# d150_z570m_rev_a.net
KiCad netlist of a schematic drawn in EAGLE
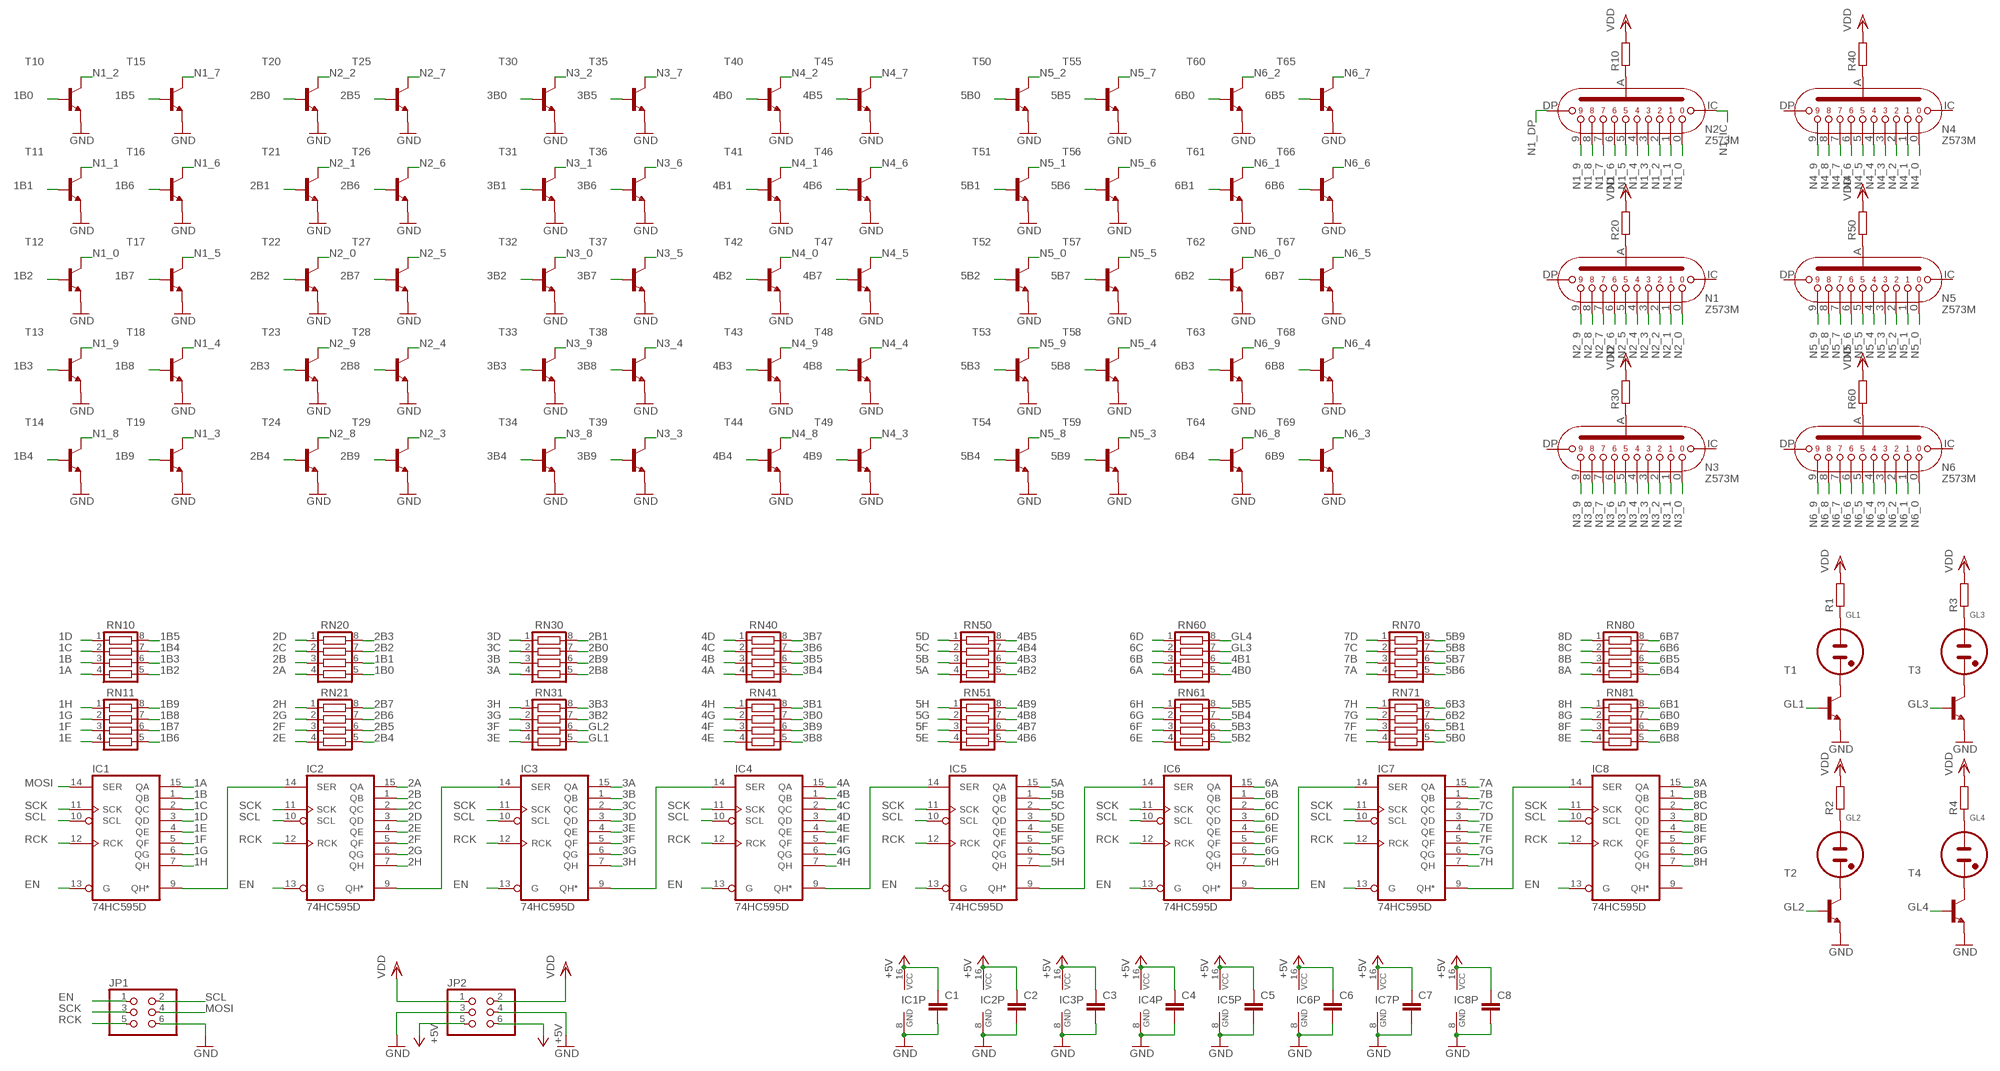
[diagram p0: schematic, sheet 1]

(export (version "E")
  (design (tool "Eeschema 10.0.6"))
  (components
    (comp (ref "C1")
      (value "C-EUC0603")
      (footprint "eagle-import:C0603")
      (libsource (lib "eagle-import") (part "C-EUC0603"))
    )
    (comp (ref "C2")
      (value "C-EUC0603")
      (footprint "eagle-import:C0603")
      (libsource (lib "eagle-import") (part "C-EUC0603"))
    )
    (comp (ref "C3")
      (value "C-EUC0603")
      (footprint "eagle-import:C0603")
      (libsource (lib "eagle-import") (part "C-EUC0603"))
    )
    (comp (ref "C4")
      (value "C-EUC0603")
      (footprint "eagle-import:C0603")
      (libsource (lib "eagle-import") (part "C-EUC0603"))
    )
    (comp (ref "C5")
      (value "C-EUC0603")
      (footprint "eagle-import:C0603")
      (libsource (lib "eagle-import") (part "C-EUC0603"))
    )
    (comp (ref "C6")
      (value "C-EUC0603")
      (footprint "eagle-import:C0603")
      (libsource (lib "eagle-import") (part "C-EUC0603"))
    )
    (comp (ref "C7")
      (value "C-EUC0603")
      (footprint "eagle-import:C0603")
      (libsource (lib "eagle-import") (part "C-EUC0603"))
    )
    (comp (ref "C8")
      (value "C-EUC0603")
      (footprint "eagle-import:C0603")
      (libsource (lib "eagle-import") (part "C-EUC0603"))
    )
    (comp (ref "GL1")
      (value "NE2-NEON-BULB-DRILL")
      (footprint "eagle-import:NE2-NEON-BULB-DRILL")
      (libsource (lib "eagle-import") (part "NE2-NEON-BULB-DRILL"))
    )
    (comp (ref "GL2")
      (value "NE2-NEON-BULB-DRILL")
      (footprint "eagle-import:NE2-NEON-BULB-DRILL")
      (libsource (lib "eagle-import") (part "NE2-NEON-BULB-DRILL"))
    )
    (comp (ref "GL3")
      (value "NE2-NEON-BULB-DRILL")
      (footprint "eagle-import:NE2-NEON-BULB-DRILL")
      (libsource (lib "eagle-import") (part "NE2-NEON-BULB-DRILL"))
    )
    (comp (ref "GL4")
      (value "NE2-NEON-BULB-DRILL")
      (footprint "eagle-import:NE2-NEON-BULB-DRILL")
      (libsource (lib "eagle-import") (part "NE2-NEON-BULB-DRILL"))
    )
    (comp (ref "IC1")
      (value "74HC595D")
      (footprint "eagle-import:SO16")
      (libsource (lib "eagle-import") (part "74595DHC"))
    )
    (comp (ref "IC2")
      (value "74HC595D")
      (footprint "eagle-import:SO16")
      (libsource (lib "eagle-import") (part "74595DHC"))
    )
    (comp (ref "IC3")
      (value "74HC595D")
      (footprint "eagle-import:SO16")
      (libsource (lib "eagle-import") (part "74595DHC"))
    )
    (comp (ref "IC4")
      (value "74HC595D")
      (footprint "eagle-import:SO16")
      (libsource (lib "eagle-import") (part "74595DHC"))
    )
    (comp (ref "IC5")
      (value "74HC595D")
      (footprint "eagle-import:SO16")
      (libsource (lib "eagle-import") (part "74595DHC"))
    )
    (comp (ref "IC6")
      (value "74HC595D")
      (footprint "eagle-import:SO16")
      (libsource (lib "eagle-import") (part "74595DHC"))
    )
    (comp (ref "IC7")
      (value "74HC595D")
      (footprint "eagle-import:SO16")
      (libsource (lib "eagle-import") (part "74595DHC"))
    )
    (comp (ref "IC8")
      (value "74HC595D")
      (footprint "eagle-import:SO16")
      (libsource (lib "eagle-import") (part "74595DHC"))
    )
    (comp (ref "JP1")
      (value "PINHD-2X3_2.54-SMD")
      (footprint "eagle-import:2X03SMD")
      (libsource (lib "eagle-import") (part "PINHD-2X3_2.54-SMD"))
    )
    (comp (ref "JP2")
      (value "PINHD-2X3_2.54-SMD")
      (footprint "eagle-import:2X03SMD")
      (libsource (lib "eagle-import") (part "PINHD-2X3_2.54-SMD"))
    )
    (comp (ref "N1")
      (value "Z573M")
      (footprint "eagle-import:Z57XX")
      (libsource (lib "eagle-import") (part "Z573M"))
    )
    (comp (ref "N2")
      (value "Z573M")
      (footprint "eagle-import:Z57XX")
      (libsource (lib "eagle-import") (part "Z573M"))
    )
    (comp (ref "N3")
      (value "Z573M")
      (footprint "eagle-import:Z57XX")
      (libsource (lib "eagle-import") (part "Z573M"))
    )
    (comp (ref "N4")
      (value "Z573M")
      (footprint "eagle-import:Z57XX")
      (libsource (lib "eagle-import") (part "Z573M"))
    )
    (comp (ref "N5")
      (value "Z573M")
      (footprint "eagle-import:Z57XX")
      (libsource (lib "eagle-import") (part "Z573M"))
    )
    (comp (ref "N6")
      (value "Z573M")
      (footprint "eagle-import:Z57XX")
      (libsource (lib "eagle-import") (part "Z573M"))
    )
    (comp (ref "R1")
      (value "R-EU_R0603")
      (footprint "eagle-import:R0603")
      (libsource (lib "eagle-import") (part "R-EU_R0603"))
    )
    (comp (ref "R2")
      (value "R-EU_R0603")
      (footprint "eagle-import:R0603")
      (libsource (lib "eagle-import") (part "R-EU_R0603"))
    )
    (comp (ref "R3")
      (value "R-EU_R0603")
      (footprint "eagle-import:R0603")
      (libsource (lib "eagle-import") (part "R-EU_R0603"))
    )
    (comp (ref "R4")
      (value "R-EU_R0603")
      (footprint "eagle-import:R0603")
      (libsource (lib "eagle-import") (part "R-EU_R0603"))
    )
    (comp (ref "R10")
      (value "R-EU_R0603")
      (footprint "eagle-import:R0603")
      (libsource (lib "eagle-import") (part "R-EU_R0603"))
    )
    (comp (ref "R20")
      (value "R-EU_R0603")
      (footprint "eagle-import:R0603")
      (libsource (lib "eagle-import") (part "R-EU_R0603"))
    )
    (comp (ref "R30")
      (value "R-EU_R0603")
      (footprint "eagle-import:R0603")
      (libsource (lib "eagle-import") (part "R-EU_R0603"))
    )
    (comp (ref "R40")
      (value "R-EU_R0603")
      (footprint "eagle-import:R0603")
      (libsource (lib "eagle-import") (part "R-EU_R0603"))
    )
    (comp (ref "R50")
      (value "R-EU_R0603")
      (footprint "eagle-import:R0603")
      (libsource (lib "eagle-import") (part "R-EU_R0603"))
    )
    (comp (ref "R60")
      (value "R-EU_R0603")
      (footprint "eagle-import:R0603")
      (libsource (lib "eagle-import") (part "R-EU_R0603"))
    )
    (comp (ref "RN10")
      (value "CTS742C083")
      (footprint "eagle-import:CTS742C083")
      (fields (field (name "OC_FARNELL") "unknown") (field (name "OC_NEWARK") "unknown"))
      (libsource (lib "eagle-import") (part "CTS742C083"))
    )
    (comp (ref "RN11")
      (value "CTS742C083")
      (footprint "eagle-import:CTS742C083")
      (fields (field (name "OC_FARNELL") "unknown") (field (name "OC_NEWARK") "unknown"))
      (libsource (lib "eagle-import") (part "CTS742C083"))
    )
    (comp (ref "RN20")
      (value "CTS742C083")
      (footprint "eagle-import:CTS742C083")
      (fields (field (name "OC_FARNELL") "unknown") (field (name "OC_NEWARK") "unknown"))
      (libsource (lib "eagle-import") (part "CTS742C083"))
    )
    (comp (ref "RN21")
      (value "CTS742C083")
      (footprint "eagle-import:CTS742C083")
      (fields (field (name "OC_FARNELL") "unknown") (field (name "OC_NEWARK") "unknown"))
      (libsource (lib "eagle-import") (part "CTS742C083"))
    )
    (comp (ref "RN30")
      (value "CTS742C083")
      (footprint "eagle-import:CTS742C083")
      (fields (field (name "OC_FARNELL") "unknown") (field (name "OC_NEWARK") "unknown"))
      (libsource (lib "eagle-import") (part "CTS742C083"))
    )
    (comp (ref "RN31")
      (value "CTS742C083")
      (footprint "eagle-import:CTS742C083")
      (fields (field (name "OC_FARNELL") "unknown") (field (name "OC_NEWARK") "unknown"))
      (libsource (lib "eagle-import") (part "CTS742C083"))
    )
    (comp (ref "RN40")
      (value "CTS742C083")
      (footprint "eagle-import:CTS742C083")
      (fields (field (name "OC_FARNELL") "unknown") (field (name "OC_NEWARK") "unknown"))
      (libsource (lib "eagle-import") (part "CTS742C083"))
    )
    (comp (ref "RN41")
      (value "CTS742C083")
      (footprint "eagle-import:CTS742C083")
      (fields (field (name "OC_FARNELL") "unknown") (field (name "OC_NEWARK") "unknown"))
      (libsource (lib "eagle-import") (part "CTS742C083"))
    )
    (comp (ref "RN50")
      (value "CTS742C083")
      (footprint "eagle-import:CTS742C083")
      (fields (field (name "OC_FARNELL") "unknown") (field (name "OC_NEWARK") "unknown"))
      (libsource (lib "eagle-import") (part "CTS742C083"))
    )
    (comp (ref "RN51")
      (value "CTS742C083")
      (footprint "eagle-import:CTS742C083")
      (fields (field (name "OC_FARNELL") "unknown") (field (name "OC_NEWARK") "unknown"))
      (libsource (lib "eagle-import") (part "CTS742C083"))
    )
    (comp (ref "RN60")
      (value "CTS742C083")
      (footprint "eagle-import:CTS742C083")
      (fields (field (name "OC_FARNELL") "unknown") (field (name "OC_NEWARK") "unknown"))
      (libsource (lib "eagle-import") (part "CTS742C083"))
    )
    (comp (ref "RN61")
      (value "CTS742C083")
      (footprint "eagle-import:CTS742C083")
      (fields (field (name "OC_FARNELL") "unknown") (field (name "OC_NEWARK") "unknown"))
      (libsource (lib "eagle-import") (part "CTS742C083"))
    )
    (comp (ref "RN70")
      (value "CTS742C083")
      (footprint "eagle-import:CTS742C083")
      (fields (field (name "OC_FARNELL") "unknown") (field (name "OC_NEWARK") "unknown"))
      (libsource (lib "eagle-import") (part "CTS742C083"))
    )
    (comp (ref "RN71")
      (value "CTS742C083")
      (footprint "eagle-import:CTS742C083")
      (fields (field (name "OC_FARNELL") "unknown") (field (name "OC_NEWARK") "unknown"))
      (libsource (lib "eagle-import") (part "CTS742C083"))
    )
    (comp (ref "RN80")
      (value "CTS742C083")
      (footprint "eagle-import:CTS742C083")
      (fields (field (name "OC_FARNELL") "unknown") (field (name "OC_NEWARK") "unknown"))
      (libsource (lib "eagle-import") (part "CTS742C083"))
    )
    (comp (ref "RN81")
      (value "CTS742C083")
      (footprint "eagle-import:CTS742C083")
      (fields (field (name "OC_FARNELL") "unknown") (field (name "OC_NEWARK") "unknown"))
      (libsource (lib "eagle-import") (part "CTS742C083"))
    )
    (comp (ref "T1")
      (value "SMBTA42")
      (footprint "eagle-import:SOT23")
      (libsource (lib "eagle-import") (part "SMBTA42"))
    )
    (comp (ref "T2")
      (value "SMBTA42")
      (footprint "eagle-import:SOT23")
      (libsource (lib "eagle-import") (part "SMBTA42"))
    )
    (comp (ref "T3")
      (value "SMBTA42")
      (footprint "eagle-import:SOT23")
      (libsource (lib "eagle-import") (part "SMBTA42"))
    )
    (comp (ref "T4")
      (value "SMBTA42")
      (footprint "eagle-import:SOT23")
      (libsource (lib "eagle-import") (part "SMBTA42"))
    )
    (comp (ref "T10")
      (value "SMBTA42")
      (footprint "eagle-import:SOT23")
      (libsource (lib "eagle-import") (part "SMBTA42"))
    )
    (comp (ref "T11")
      (value "SMBTA42")
      (footprint "eagle-import:SOT23")
      (libsource (lib "eagle-import") (part "SMBTA42"))
    )
    (comp (ref "T12")
      (value "SMBTA42")
      (footprint "eagle-import:SOT23")
      (libsource (lib "eagle-import") (part "SMBTA42"))
    )
    (comp (ref "T13")
      (value "SMBTA42")
      (footprint "eagle-import:SOT23")
      (libsource (lib "eagle-import") (part "SMBTA42"))
    )
    (comp (ref "T14")
      (value "SMBTA42")
      (footprint "eagle-import:SOT23")
      (libsource (lib "eagle-import") (part "SMBTA42"))
    )
    (comp (ref "T15")
      (value "SMBTA42")
      (footprint "eagle-import:SOT23")
      (libsource (lib "eagle-import") (part "SMBTA42"))
    )
    (comp (ref "T16")
      (value "SMBTA42")
      (footprint "eagle-import:SOT23")
      (libsource (lib "eagle-import") (part "SMBTA42"))
    )
    (comp (ref "T17")
      (value "SMBTA42")
      (footprint "eagle-import:SOT23")
      (libsource (lib "eagle-import") (part "SMBTA42"))
    )
    (comp (ref "T18")
      (value "SMBTA42")
      (footprint "eagle-import:SOT23")
      (libsource (lib "eagle-import") (part "SMBTA42"))
    )
    (comp (ref "T19")
      (value "SMBTA42")
      (footprint "eagle-import:SOT23")
      (libsource (lib "eagle-import") (part "SMBTA42"))
    )
    (comp (ref "T20")
      (value "SMBTA42")
      (footprint "eagle-import:SOT23")
      (libsource (lib "eagle-import") (part "SMBTA42"))
    )
    (comp (ref "T21")
      (value "SMBTA42")
      (footprint "eagle-import:SOT23")
      (libsource (lib "eagle-import") (part "SMBTA42"))
    )
    (comp (ref "T22")
      (value "SMBTA42")
      (footprint "eagle-import:SOT23")
      (libsource (lib "eagle-import") (part "SMBTA42"))
    )
    (comp (ref "T23")
      (value "SMBTA42")
      (footprint "eagle-import:SOT23")
      (libsource (lib "eagle-import") (part "SMBTA42"))
    )
    (comp (ref "T24")
      (value "SMBTA42")
      (footprint "eagle-import:SOT23")
      (libsource (lib "eagle-import") (part "SMBTA42"))
    )
    (comp (ref "T25")
      (value "SMBTA42")
      (footprint "eagle-import:SOT23")
      (libsource (lib "eagle-import") (part "SMBTA42"))
    )
    (comp (ref "T26")
      (value "SMBTA42")
      (footprint "eagle-import:SOT23")
      (libsource (lib "eagle-import") (part "SMBTA42"))
    )
    (comp (ref "T27")
      (value "SMBTA42")
      (footprint "eagle-import:SOT23")
      (libsource (lib "eagle-import") (part "SMBTA42"))
    )
    (comp (ref "T28")
      (value "SMBTA42")
      (footprint "eagle-import:SOT23")
      (libsource (lib "eagle-import") (part "SMBTA42"))
    )
    (comp (ref "T29")
      (value "SMBTA42")
      (footprint "eagle-import:SOT23")
      (libsource (lib "eagle-import") (part "SMBTA42"))
    )
    (comp (ref "T30")
      (value "SMBTA42")
      (footprint "eagle-import:SOT23")
      (libsource (lib "eagle-import") (part "SMBTA42"))
    )
    (comp (ref "T31")
      (value "SMBTA42")
      (footprint "eagle-import:SOT23")
      (libsource (lib "eagle-import") (part "SMBTA42"))
    )
    (comp (ref "T32")
      (value "SMBTA42")
      (footprint "eagle-import:SOT23")
      (libsource (lib "eagle-import") (part "SMBTA42"))
    )
    (comp (ref "T33")
      (value "SMBTA42")
      (footprint "eagle-import:SOT23")
      (libsource (lib "eagle-import") (part "SMBTA42"))
    )
    (comp (ref "T34")
      (value "SMBTA42")
      (footprint "eagle-import:SOT23")
      (libsource (lib "eagle-import") (part "SMBTA42"))
    )
    (comp (ref "T35")
      (value "SMBTA42")
      (footprint "eagle-import:SOT23")
      (libsource (lib "eagle-import") (part "SMBTA42"))
    )
    (comp (ref "T36")
      (value "SMBTA42")
      (footprint "eagle-import:SOT23")
      (libsource (lib "eagle-import") (part "SMBTA42"))
    )
    (comp (ref "T37")
      (value "SMBTA42")
      (footprint "eagle-import:SOT23")
      (libsource (lib "eagle-import") (part "SMBTA42"))
    )
    (comp (ref "T38")
      (value "SMBTA42")
      (footprint "eagle-import:SOT23")
      (libsource (lib "eagle-import") (part "SMBTA42"))
    )
    (comp (ref "T39")
      (value "SMBTA42")
      (footprint "eagle-import:SOT23")
      (libsource (lib "eagle-import") (part "SMBTA42"))
    )
    (comp (ref "T40")
      (value "SMBTA42")
      (footprint "eagle-import:SOT23")
      (libsource (lib "eagle-import") (part "SMBTA42"))
    )
    (comp (ref "T41")
      (value "SMBTA42")
      (footprint "eagle-import:SOT23")
      (libsource (lib "eagle-import") (part "SMBTA42"))
    )
    (comp (ref "T42")
      (value "SMBTA42")
      (footprint "eagle-import:SOT23")
      (libsource (lib "eagle-import") (part "SMBTA42"))
    )
    (comp (ref "T43")
      (value "SMBTA42")
      (footprint "eagle-import:SOT23")
      (libsource (lib "eagle-import") (part "SMBTA42"))
    )
    (comp (ref "T44")
      (value "SMBTA42")
      (footprint "eagle-import:SOT23")
      (libsource (lib "eagle-import") (part "SMBTA42"))
    )
    (comp (ref "T45")
      (value "SMBTA42")
      (footprint "eagle-import:SOT23")
      (libsource (lib "eagle-import") (part "SMBTA42"))
    )
    (comp (ref "T46")
      (value "SMBTA42")
      (footprint "eagle-import:SOT23")
      (libsource (lib "eagle-import") (part "SMBTA42"))
    )
    (comp (ref "T47")
      (value "SMBTA42")
      (footprint "eagle-import:SOT23")
      (libsource (lib "eagle-import") (part "SMBTA42"))
    )
    (comp (ref "T48")
      (value "SMBTA42")
      (footprint "eagle-import:SOT23")
      (libsource (lib "eagle-import") (part "SMBTA42"))
    )
    (comp (ref "T49")
      (value "SMBTA42")
      (footprint "eagle-import:SOT23")
      (libsource (lib "eagle-import") (part "SMBTA42"))
    )
    (comp (ref "T50")
      (value "SMBTA42")
      (footprint "eagle-import:SOT23")
      (libsource (lib "eagle-import") (part "SMBTA42"))
    )
    (comp (ref "T51")
      (value "SMBTA42")
      (footprint "eagle-import:SOT23")
      (libsource (lib "eagle-import") (part "SMBTA42"))
    )
    (comp (ref "T52")
      (value "SMBTA42")
      (footprint "eagle-import:SOT23")
      (libsource (lib "eagle-import") (part "SMBTA42"))
    )
    (comp (ref "T53")
      (value "SMBTA42")
      (footprint "eagle-import:SOT23")
      (libsource (lib "eagle-import") (part "SMBTA42"))
    )
    (comp (ref "T54")
      (value "SMBTA42")
      (footprint "eagle-import:SOT23")
      (libsource (lib "eagle-import") (part "SMBTA42"))
    )
    (comp (ref "T55")
      (value "SMBTA42")
      (footprint "eagle-import:SOT23")
      (libsource (lib "eagle-import") (part "SMBTA42"))
    )
    (comp (ref "T56")
      (value "SMBTA42")
      (footprint "eagle-import:SOT23")
      (libsource (lib "eagle-import") (part "SMBTA42"))
    )
    (comp (ref "T57")
      (value "SMBTA42")
      (footprint "eagle-import:SOT23")
      (libsource (lib "eagle-import") (part "SMBTA42"))
    )
    (comp (ref "T58")
      (value "SMBTA42")
      (footprint "eagle-import:SOT23")
      (libsource (lib "eagle-import") (part "SMBTA42"))
    )
    (comp (ref "T59")
      (value "SMBTA42")
      (footprint "eagle-import:SOT23")
      (libsource (lib "eagle-import") (part "SMBTA42"))
    )
    (comp (ref "T60")
      (value "SMBTA42")
      (footprint "eagle-import:SOT23")
      (libsource (lib "eagle-import") (part "SMBTA42"))
    )
    (comp (ref "T61")
      (value "SMBTA42")
      (footprint "eagle-import:SOT23")
      (libsource (lib "eagle-import") (part "SMBTA42"))
    )
    (comp (ref "T62")
      (value "SMBTA42")
      (footprint "eagle-import:SOT23")
      (libsource (lib "eagle-import") (part "SMBTA42"))
    )
    (comp (ref "T63")
      (value "SMBTA42")
      (footprint "eagle-import:SOT23")
      (libsource (lib "eagle-import") (part "SMBTA42"))
    )
    (comp (ref "T64")
      (value "SMBTA42")
      (footprint "eagle-import:SOT23")
      (libsource (lib "eagle-import") (part "SMBTA42"))
    )
    (comp (ref "T65")
      (value "SMBTA42")
      (footprint "eagle-import:SOT23")
      (libsource (lib "eagle-import") (part "SMBTA42"))
    )
    (comp (ref "T66")
      (value "SMBTA42")
      (footprint "eagle-import:SOT23")
      (libsource (lib "eagle-import") (part "SMBTA42"))
    )
    (comp (ref "T67")
      (value "SMBTA42")
      (footprint "eagle-import:SOT23")
      (libsource (lib "eagle-import") (part "SMBTA42"))
    )
    (comp (ref "T68")
      (value "SMBTA42")
      (footprint "eagle-import:SOT23")
      (libsource (lib "eagle-import") (part "SMBTA42"))
    )
    (comp (ref "T69")
      (value "SMBTA42")
      (footprint "eagle-import:SOT23")
      (libsource (lib "eagle-import") (part "SMBTA42"))
    )
  )
  (nets
    (net (code "1") (name "+5V") (class "Default")
      (node (ref "C1") (pin "1") (pinfunction "1_1") (pintype "passive"))
      (node (ref "C2") (pin "1") (pinfunction "1_1") (pintype "passive"))
      (node (ref "C3") (pin "1") (pinfunction "1_1") (pintype "passive"))
      (node (ref "C4") (pin "1") (pinfunction "1_1") (pintype "passive"))
      (node (ref "C5") (pin "1") (pinfunction "1_1") (pintype "passive"))
      (node (ref "C6") (pin "1") (pinfunction "1_1") (pintype "passive"))
      (node (ref "C7") (pin "1") (pinfunction "1_1") (pintype "passive"))
      (node (ref "C8") (pin "1") (pinfunction "1_1") (pintype "passive"))
      (node (ref "IC1") (pin "16") (pinfunction "VCC_16") (pintype "power_in"))
      (node (ref "IC2") (pin "16") (pinfunction "VCC_16") (pintype "power_in"))
      (node (ref "IC3") (pin "16") (pinfunction "VCC_16") (pintype "power_in"))
      (node (ref "IC4") (pin "16") (pinfunction "VCC_16") (pintype "power_in"))
      (node (ref "IC5") (pin "16") (pinfunction "VCC_16") (pintype "power_in"))
      (node (ref "IC6") (pin "16") (pinfunction "VCC_16") (pintype "power_in"))
      (node (ref "IC7") (pin "16") (pinfunction "VCC_16") (pintype "power_in"))
      (node (ref "IC8") (pin "16") (pinfunction "VCC_16") (pintype "power_in"))
      (node (ref "JP2") (pin "5") (pinfunction "5_5") (pintype "passive"))
      (node (ref "JP2") (pin "6") (pinfunction "6_6") (pintype "passive"))
    )
    (net (code "2") (name "/1A") (class "Default")
      (node (ref "IC1") (pin "15") (pinfunction "QA_15") (pintype "tri_state"))
      (node (ref "RN10") (pin "4") (pinfunction "4_4") (pintype "passive"))
    )
    (net (code "3") (name "/1B") (class "Default")
      (node (ref "IC1") (pin "1") (pinfunction "QB_1") (pintype "tri_state"))
      (node (ref "RN10") (pin "3") (pinfunction "3_3") (pintype "passive"))
    )
    (net (code "4") (name "/1B0") (class "Default")
      (node (ref "RN20") (pin "5") (pinfunction "5_5") (pintype "passive"))
      (node (ref "T10") (pin "1") (pinfunction "B_1") (pintype "passive"))
    )
    (net (code "5") (name "/1B1") (class "Default")
      (node (ref "RN20") (pin "6") (pinfunction "6_6") (pintype "passive"))
      (node (ref "T11") (pin "1") (pinfunction "B_1") (pintype "passive"))
    )
    (net (code "6") (name "/1B2") (class "Default")
      (node (ref "RN10") (pin "5") (pinfunction "5_5") (pintype "passive"))
      (node (ref "T12") (pin "1") (pinfunction "B_1") (pintype "passive"))
    )
    (net (code "7") (name "/1B3") (class "Default")
      (node (ref "RN10") (pin "6") (pinfunction "6_6") (pintype "passive"))
      (node (ref "T13") (pin "1") (pinfunction "B_1") (pintype "passive"))
    )
    (net (code "8") (name "/1B4") (class "Default")
      (node (ref "RN10") (pin "7") (pinfunction "7_7") (pintype "passive"))
      (node (ref "T14") (pin "1") (pinfunction "B_1") (pintype "passive"))
    )
    (net (code "9") (name "/1B5") (class "Default")
      (node (ref "RN10") (pin "8") (pinfunction "8_8") (pintype "passive"))
      (node (ref "T15") (pin "1") (pinfunction "B_1") (pintype "passive"))
    )
    (net (code "10") (name "/1B6") (class "Default")
      (node (ref "RN11") (pin "5") (pinfunction "5_5") (pintype "passive"))
      (node (ref "T16") (pin "1") (pinfunction "B_1") (pintype "passive"))
    )
    (net (code "11") (name "/1B7") (class "Default")
      (node (ref "RN11") (pin "6") (pinfunction "6_6") (pintype "passive"))
      (node (ref "T17") (pin "1") (pinfunction "B_1") (pintype "passive"))
    )
    (net (code "12") (name "/1B8") (class "Default")
      (node (ref "RN11") (pin "7") (pinfunction "7_7") (pintype "passive"))
      (node (ref "T18") (pin "1") (pinfunction "B_1") (pintype "passive"))
    )
    (net (code "13") (name "/1B9") (class "Default")
      (node (ref "RN11") (pin "8") (pinfunction "8_8") (pintype "passive"))
      (node (ref "T19") (pin "1") (pinfunction "B_1") (pintype "passive"))
    )
    (net (code "14") (name "/1C") (class "Default")
      (node (ref "IC1") (pin "2") (pinfunction "QC_2") (pintype "tri_state"))
      (node (ref "RN10") (pin "2") (pinfunction "2_2") (pintype "passive"))
    )
    (net (code "15") (name "/1D") (class "Default")
      (node (ref "IC1") (pin "3") (pinfunction "QD_3") (pintype "tri_state"))
      (node (ref "RN10") (pin "1") (pinfunction "1_1") (pintype "passive"))
    )
    (net (code "16") (name "/1E") (class "Default")
      (node (ref "IC1") (pin "4") (pinfunction "QE_4") (pintype "tri_state"))
      (node (ref "RN11") (pin "4") (pinfunction "4_4") (pintype "passive"))
    )
    (net (code "17") (name "/1F") (class "Default")
      (node (ref "IC1") (pin "5") (pinfunction "QF_5") (pintype "tri_state"))
      (node (ref "RN11") (pin "3") (pinfunction "3_3") (pintype "passive"))
    )
    (net (code "18") (name "/1G") (class "Default")
      (node (ref "IC1") (pin "6") (pinfunction "QG_6") (pintype "tri_state"))
      (node (ref "RN11") (pin "2") (pinfunction "2_2") (pintype "passive"))
    )
    (net (code "19") (name "/1H") (class "Default")
      (node (ref "IC1") (pin "7") (pinfunction "QH_7") (pintype "tri_state"))
      (node (ref "RN11") (pin "1") (pinfunction "1_1") (pintype "passive"))
    )
    (net (code "20") (name "/2A") (class "Default")
      (node (ref "IC2") (pin "15") (pinfunction "QA_15") (pintype "tri_state"))
      (node (ref "RN20") (pin "4") (pinfunction "4_4") (pintype "passive"))
    )
    (net (code "21") (name "/2B") (class "Default")
      (node (ref "IC2") (pin "1") (pinfunction "QB_1") (pintype "tri_state"))
      (node (ref "RN20") (pin "3") (pinfunction "3_3") (pintype "passive"))
    )
    (net (code "22") (name "/2B0") (class "Default")
      (node (ref "RN30") (pin "7") (pinfunction "7_7") (pintype "passive"))
      (node (ref "T20") (pin "1") (pinfunction "B_1") (pintype "passive"))
    )
    (net (code "23") (name "/2B1") (class "Default")
      (node (ref "RN30") (pin "8") (pinfunction "8_8") (pintype "passive"))
      (node (ref "T21") (pin "1") (pinfunction "B_1") (pintype "passive"))
    )
    (net (code "24") (name "/2B2") (class "Default")
      (node (ref "RN20") (pin "7") (pinfunction "7_7") (pintype "passive"))
      (node (ref "T22") (pin "1") (pinfunction "B_1") (pintype "passive"))
    )
    (net (code "25") (name "/2B3") (class "Default")
      (node (ref "RN20") (pin "8") (pinfunction "8_8") (pintype "passive"))
      (node (ref "T23") (pin "1") (pinfunction "B_1") (pintype "passive"))
    )
    (net (code "26") (name "/2B4") (class "Default")
      (node (ref "RN21") (pin "5") (pinfunction "5_5") (pintype "passive"))
      (node (ref "T24") (pin "1") (pinfunction "B_1") (pintype "passive"))
    )
    (net (code "27") (name "/2B5") (class "Default")
      (node (ref "RN21") (pin "6") (pinfunction "6_6") (pintype "passive"))
      (node (ref "T25") (pin "1") (pinfunction "B_1") (pintype "passive"))
    )
    (net (code "28") (name "/2B6") (class "Default")
      (node (ref "RN21") (pin "7") (pinfunction "7_7") (pintype "passive"))
      (node (ref "T26") (pin "1") (pinfunction "B_1") (pintype "passive"))
    )
    (net (code "29") (name "/2B7") (class "Default")
      (node (ref "RN21") (pin "8") (pinfunction "8_8") (pintype "passive"))
      (node (ref "T27") (pin "1") (pinfunction "B_1") (pintype "passive"))
    )
    (net (code "30") (name "/2B8") (class "Default")
      (node (ref "RN30") (pin "5") (pinfunction "5_5") (pintype "passive"))
      (node (ref "T28") (pin "1") (pinfunction "B_1") (pintype "passive"))
    )
    (net (code "31") (name "/2B9") (class "Default")
      (node (ref "RN30") (pin "6") (pinfunction "6_6") (pintype "passive"))
      (node (ref "T29") (pin "1") (pinfunction "B_1") (pintype "passive"))
    )
    (net (code "32") (name "/2C") (class "Default")
      (node (ref "IC2") (pin "2") (pinfunction "QC_2") (pintype "tri_state"))
      (node (ref "RN20") (pin "2") (pinfunction "2_2") (pintype "passive"))
    )
    (net (code "33") (name "/2D") (class "Default")
      (node (ref "IC2") (pin "3") (pinfunction "QD_3") (pintype "tri_state"))
      (node (ref "RN20") (pin "1") (pinfunction "1_1") (pintype "passive"))
    )
    (net (code "34") (name "/2E") (class "Default")
      (node (ref "IC2") (pin "4") (pinfunction "QE_4") (pintype "tri_state"))
      (node (ref "RN21") (pin "4") (pinfunction "4_4") (pintype "passive"))
    )
    (net (code "35") (name "/2F") (class "Default")
      (node (ref "IC2") (pin "5") (pinfunction "QF_5") (pintype "tri_state"))
      (node (ref "RN21") (pin "3") (pinfunction "3_3") (pintype "passive"))
    )
    (net (code "36") (name "/2G") (class "Default")
      (node (ref "IC2") (pin "6") (pinfunction "QG_6") (pintype "tri_state"))
      (node (ref "RN21") (pin "2") (pinfunction "2_2") (pintype "passive"))
    )
    (net (code "37") (name "/2H") (class "Default")
      (node (ref "IC2") (pin "7") (pinfunction "QH_7") (pintype "tri_state"))
      (node (ref "RN21") (pin "1") (pinfunction "1_1") (pintype "passive"))
    )
    (net (code "38") (name "/3A") (class "Default")
      (node (ref "IC3") (pin "15") (pinfunction "QA_15") (pintype "tri_state"))
      (node (ref "RN30") (pin "4") (pinfunction "4_4") (pintype "passive"))
    )
    (net (code "39") (name "/3B") (class "Default")
      (node (ref "IC3") (pin "1") (pinfunction "QB_1") (pintype "tri_state"))
      (node (ref "RN30") (pin "3") (pinfunction "3_3") (pintype "passive"))
    )
    (net (code "40") (name "/3B0") (class "Default")
      (node (ref "RN41") (pin "7") (pinfunction "7_7") (pintype "passive"))
      (node (ref "T30") (pin "1") (pinfunction "B_1") (pintype "passive"))
    )
    (net (code "41") (name "/3B1") (class "Default")
      (node (ref "RN41") (pin "8") (pinfunction "8_8") (pintype "passive"))
      (node (ref "T31") (pin "1") (pinfunction "B_1") (pintype "passive"))
    )
    (net (code "42") (name "/3B2") (class "Default")
      (node (ref "RN31") (pin "7") (pinfunction "7_7") (pintype "passive"))
      (node (ref "T32") (pin "1") (pinfunction "B_1") (pintype "passive"))
    )
    (net (code "43") (name "/3B3") (class "Default")
      (node (ref "RN31") (pin "8") (pinfunction "8_8") (pintype "passive"))
      (node (ref "T33") (pin "1") (pinfunction "B_1") (pintype "passive"))
    )
    (net (code "44") (name "/3B4") (class "Default")
      (node (ref "RN40") (pin "5") (pinfunction "5_5") (pintype "passive"))
      (node (ref "T34") (pin "1") (pinfunction "B_1") (pintype "passive"))
    )
    (net (code "45") (name "/3B5") (class "Default")
      (node (ref "RN40") (pin "6") (pinfunction "6_6") (pintype "passive"))
      (node (ref "T35") (pin "1") (pinfunction "B_1") (pintype "passive"))
    )
    (net (code "46") (name "/3B6") (class "Default")
      (node (ref "RN40") (pin "7") (pinfunction "7_7") (pintype "passive"))
      (node (ref "T36") (pin "1") (pinfunction "B_1") (pintype "passive"))
    )
    (net (code "47") (name "/3B7") (class "Default")
      (node (ref "RN40") (pin "8") (pinfunction "8_8") (pintype "passive"))
      (node (ref "T37") (pin "1") (pinfunction "B_1") (pintype "passive"))
    )
    (net (code "48") (name "/3B8") (class "Default")
      (node (ref "RN41") (pin "5") (pinfunction "5_5") (pintype "passive"))
      (node (ref "T38") (pin "1") (pinfunction "B_1") (pintype "passive"))
    )
    (net (code "49") (name "/3B9") (class "Default")
      (node (ref "RN41") (pin "6") (pinfunction "6_6") (pintype "passive"))
      (node (ref "T39") (pin "1") (pinfunction "B_1") (pintype "passive"))
    )
    (net (code "50") (name "/3C") (class "Default")
      (node (ref "IC3") (pin "2") (pinfunction "QC_2") (pintype "tri_state"))
      (node (ref "RN30") (pin "2") (pinfunction "2_2") (pintype "passive"))
    )
    (net (code "51") (name "/3D") (class "Default")
      (node (ref "IC3") (pin "3") (pinfunction "QD_3") (pintype "tri_state"))
      (node (ref "RN30") (pin "1") (pinfunction "1_1") (pintype "passive"))
    )
    (net (code "52") (name "/3E") (class "Default")
      (node (ref "IC3") (pin "4") (pinfunction "QE_4") (pintype "tri_state"))
      (node (ref "RN31") (pin "4") (pinfunction "4_4") (pintype "passive"))
    )
    (net (code "53") (name "/3F") (class "Default")
      (node (ref "IC3") (pin "5") (pinfunction "QF_5") (pintype "tri_state"))
      (node (ref "RN31") (pin "3") (pinfunction "3_3") (pintype "passive"))
    )
    (net (code "54") (name "/3G") (class "Default")
      (node (ref "IC3") (pin "6") (pinfunction "QG_6") (pintype "tri_state"))
      (node (ref "RN31") (pin "2") (pinfunction "2_2") (pintype "passive"))
    )
    (net (code "55") (name "/3H") (class "Default")
      (node (ref "IC3") (pin "7") (pinfunction "QH_7") (pintype "tri_state"))
      (node (ref "RN31") (pin "1") (pinfunction "1_1") (pintype "passive"))
    )
    (net (code "56") (name "/4A") (class "Default")
      (node (ref "IC4") (pin "15") (pinfunction "QA_15") (pintype "tri_state"))
      (node (ref "RN40") (pin "4") (pinfunction "4_4") (pintype "passive"))
    )
    (net (code "57") (name "/4B") (class "Default")
      (node (ref "IC4") (pin "1") (pinfunction "QB_1") (pintype "tri_state"))
      (node (ref "RN40") (pin "3") (pinfunction "3_3") (pintype "passive"))
    )
    (net (code "58") (name "/4B0") (class "Default")
      (node (ref "RN60") (pin "5") (pinfunction "5_5") (pintype "passive"))
      (node (ref "T40") (pin "1") (pinfunction "B_1") (pintype "passive"))
    )
    (net (code "59") (name "/4B1") (class "Default")
      (node (ref "RN60") (pin "6") (pinfunction "6_6") (pintype "passive"))
      (node (ref "T41") (pin "1") (pinfunction "B_1") (pintype "passive"))
    )
    (net (code "60") (name "/4B2") (class "Default")
      (node (ref "RN50") (pin "5") (pinfunction "5_5") (pintype "passive"))
      (node (ref "T42") (pin "1") (pinfunction "B_1") (pintype "passive"))
    )
    (net (code "61") (name "/4B3") (class "Default")
      (node (ref "RN50") (pin "6") (pinfunction "6_6") (pintype "passive"))
      (node (ref "T43") (pin "1") (pinfunction "B_1") (pintype "passive"))
    )
    (net (code "62") (name "/4B4") (class "Default")
      (node (ref "RN50") (pin "7") (pinfunction "7_7") (pintype "passive"))
      (node (ref "T44") (pin "1") (pinfunction "B_1") (pintype "passive"))
    )
    (net (code "63") (name "/4B5") (class "Default")
      (node (ref "RN50") (pin "8") (pinfunction "8_8") (pintype "passive"))
      (node (ref "T45") (pin "1") (pinfunction "B_1") (pintype "passive"))
    )
    (net (code "64") (name "/4B6") (class "Default")
      (node (ref "RN51") (pin "5") (pinfunction "5_5") (pintype "passive"))
      (node (ref "T46") (pin "1") (pinfunction "B_1") (pintype "passive"))
    )
    (net (code "65") (name "/4B7") (class "Default")
      (node (ref "RN51") (pin "6") (pinfunction "6_6") (pintype "passive"))
      (node (ref "T47") (pin "1") (pinfunction "B_1") (pintype "passive"))
    )
    (net (code "66") (name "/4B8") (class "Default")
      (node (ref "RN51") (pin "7") (pinfunction "7_7") (pintype "passive"))
      (node (ref "T48") (pin "1") (pinfunction "B_1") (pintype "passive"))
    )
    (net (code "67") (name "/4B9") (class "Default")
      (node (ref "RN51") (pin "8") (pinfunction "8_8") (pintype "passive"))
      (node (ref "T49") (pin "1") (pinfunction "B_1") (pintype "passive"))
    )
    (net (code "68") (name "/4C") (class "Default")
      (node (ref "IC4") (pin "2") (pinfunction "QC_2") (pintype "tri_state"))
      (node (ref "RN40") (pin "2") (pinfunction "2_2") (pintype "passive"))
    )
    (net (code "69") (name "/4D") (class "Default")
      (node (ref "IC4") (pin "3") (pinfunction "QD_3") (pintype "tri_state"))
      (node (ref "RN40") (pin "1") (pinfunction "1_1") (pintype "passive"))
    )
    (net (code "70") (name "/4E") (class "Default")
      (node (ref "IC4") (pin "4") (pinfunction "QE_4") (pintype "tri_state"))
      (node (ref "RN41") (pin "4") (pinfunction "4_4") (pintype "passive"))
    )
    (net (code "71") (name "/4F") (class "Default")
      (node (ref "IC4") (pin "5") (pinfunction "QF_5") (pintype "tri_state"))
      (node (ref "RN41") (pin "3") (pinfunction "3_3") (pintype "passive"))
    )
    (net (code "72") (name "/4G") (class "Default")
      (node (ref "IC4") (pin "6") (pinfunction "QG_6") (pintype "tri_state"))
      (node (ref "RN41") (pin "2") (pinfunction "2_2") (pintype "passive"))
    )
    (net (code "73") (name "/4H") (class "Default")
      (node (ref "IC4") (pin "7") (pinfunction "QH_7") (pintype "tri_state"))
      (node (ref "RN41") (pin "1") (pinfunction "1_1") (pintype "passive"))
    )
    (net (code "74") (name "/5A") (class "Default")
      (node (ref "IC5") (pin "15") (pinfunction "QA_15") (pintype "tri_state"))
      (node (ref "RN50") (pin "4") (pinfunction "4_4") (pintype "passive"))
    )
    (net (code "75") (name "/5B") (class "Default")
      (node (ref "IC5") (pin "1") (pinfunction "QB_1") (pintype "tri_state"))
      (node (ref "RN50") (pin "3") (pinfunction "3_3") (pintype "passive"))
    )
    (net (code "76") (name "/5B0") (class "Default")
      (node (ref "RN71") (pin "5") (pinfunction "5_5") (pintype "passive"))
      (node (ref "T50") (pin "1") (pinfunction "B_1") (pintype "passive"))
    )
    (net (code "77") (name "/5B1") (class "Default")
      (node (ref "RN71") (pin "6") (pinfunction "6_6") (pintype "passive"))
      (node (ref "T51") (pin "1") (pinfunction "B_1") (pintype "passive"))
    )
    (net (code "78") (name "/5B2") (class "Default")
      (node (ref "RN61") (pin "5") (pinfunction "5_5") (pintype "passive"))
      (node (ref "T52") (pin "1") (pinfunction "B_1") (pintype "passive"))
    )
    (net (code "79") (name "/5B3") (class "Default")
      (node (ref "RN61") (pin "6") (pinfunction "6_6") (pintype "passive"))
      (node (ref "T53") (pin "1") (pinfunction "B_1") (pintype "passive"))
    )
    (net (code "80") (name "/5B4") (class "Default")
      (node (ref "RN61") (pin "7") (pinfunction "7_7") (pintype "passive"))
      (node (ref "T54") (pin "1") (pinfunction "B_1") (pintype "passive"))
    )
    (net (code "81") (name "/5B5") (class "Default")
      (node (ref "RN61") (pin "8") (pinfunction "8_8") (pintype "passive"))
      (node (ref "T55") (pin "1") (pinfunction "B_1") (pintype "passive"))
    )
    (net (code "82") (name "/5B6") (class "Default")
      (node (ref "RN70") (pin "5") (pinfunction "5_5") (pintype "passive"))
      (node (ref "T56") (pin "1") (pinfunction "B_1") (pintype "passive"))
    )
    (net (code "83") (name "/5B7") (class "Default")
      (node (ref "RN70") (pin "6") (pinfunction "6_6") (pintype "passive"))
      (node (ref "T57") (pin "1") (pinfunction "B_1") (pintype "passive"))
    )
    (net (code "84") (name "/5B8") (class "Default")
      (node (ref "RN70") (pin "7") (pinfunction "7_7") (pintype "passive"))
      (node (ref "T58") (pin "1") (pinfunction "B_1") (pintype "passive"))
    )
    (net (code "85") (name "/5B9") (class "Default")
      (node (ref "RN70") (pin "8") (pinfunction "8_8") (pintype "passive"))
      (node (ref "T59") (pin "1") (pinfunction "B_1") (pintype "passive"))
    )
    (net (code "86") (name "/5C") (class "Default")
      (node (ref "IC5") (pin "2") (pinfunction "QC_2") (pintype "tri_state"))
      (node (ref "RN50") (pin "2") (pinfunction "2_2") (pintype "passive"))
    )
    (net (code "87") (name "/5D") (class "Default")
      (node (ref "IC5") (pin "3") (pinfunction "QD_3") (pintype "tri_state"))
      (node (ref "RN50") (pin "1") (pinfunction "1_1") (pintype "passive"))
    )
    (net (code "88") (name "/5E") (class "Default")
      (node (ref "IC5") (pin "4") (pinfunction "QE_4") (pintype "tri_state"))
      (node (ref "RN51") (pin "4") (pinfunction "4_4") (pintype "passive"))
    )
    (net (code "89") (name "/5F") (class "Default")
      (node (ref "IC5") (pin "5") (pinfunction "QF_5") (pintype "tri_state"))
      (node (ref "RN51") (pin "3") (pinfunction "3_3") (pintype "passive"))
    )
    (net (code "90") (name "/5G") (class "Default")
      (node (ref "IC5") (pin "6") (pinfunction "QG_6") (pintype "tri_state"))
      (node (ref "RN51") (pin "2") (pinfunction "2_2") (pintype "passive"))
    )
    (net (code "91") (name "/5H") (class "Default")
      (node (ref "IC5") (pin "7") (pinfunction "QH_7") (pintype "tri_state"))
      (node (ref "RN51") (pin "1") (pinfunction "1_1") (pintype "passive"))
    )
    (net (code "92") (name "/6A") (class "Default")
      (node (ref "IC6") (pin "15") (pinfunction "QA_15") (pintype "tri_state"))
      (node (ref "RN60") (pin "4") (pinfunction "4_4") (pintype "passive"))
    )
    (net (code "93") (name "/6B") (class "Default")
      (node (ref "IC6") (pin "1") (pinfunction "QB_1") (pintype "tri_state"))
      (node (ref "RN60") (pin "3") (pinfunction "3_3") (pintype "passive"))
    )
    (net (code "94") (name "/6B0") (class "Default")
      (node (ref "RN81") (pin "7") (pinfunction "7_7") (pintype "passive"))
      (node (ref "T60") (pin "1") (pinfunction "B_1") (pintype "passive"))
    )
    (net (code "95") (name "/6B1") (class "Default")
      (node (ref "RN81") (pin "8") (pinfunction "8_8") (pintype "passive"))
      (node (ref "T61") (pin "1") (pinfunction "B_1") (pintype "passive"))
    )
    (net (code "96") (name "/6B2") (class "Default")
      (node (ref "RN71") (pin "7") (pinfunction "7_7") (pintype "passive"))
      (node (ref "T62") (pin "1") (pinfunction "B_1") (pintype "passive"))
    )
    (net (code "97") (name "/6B3") (class "Default")
      (node (ref "RN71") (pin "8") (pinfunction "8_8") (pintype "passive"))
      (node (ref "T63") (pin "1") (pinfunction "B_1") (pintype "passive"))
    )
    (net (code "98") (name "/6B4") (class "Default")
      (node (ref "RN80") (pin "5") (pinfunction "5_5") (pintype "passive"))
      (node (ref "T64") (pin "1") (pinfunction "B_1") (pintype "passive"))
    )
    (net (code "99") (name "/6B5") (class "Default")
      (node (ref "RN80") (pin "6") (pinfunction "6_6") (pintype "passive"))
      (node (ref "T65") (pin "1") (pinfunction "B_1") (pintype "passive"))
    )
    (net (code "100") (name "/6B6") (class "Default")
      (node (ref "RN80") (pin "7") (pinfunction "7_7") (pintype "passive"))
      (node (ref "T66") (pin "1") (pinfunction "B_1") (pintype "passive"))
    )
    (net (code "101") (name "/6B7") (class "Default")
      (node (ref "RN80") (pin "8") (pinfunction "8_8") (pintype "passive"))
      (node (ref "T67") (pin "1") (pinfunction "B_1") (pintype "passive"))
    )
    (net (code "102") (name "/6B8") (class "Default")
      (node (ref "RN81") (pin "5") (pinfunction "5_5") (pintype "passive"))
      (node (ref "T68") (pin "1") (pinfunction "B_1") (pintype "passive"))
    )
    (net (code "103") (name "/6B9") (class "Default")
      (node (ref "RN81") (pin "6") (pinfunction "6_6") (pintype "passive"))
      (node (ref "T69") (pin "1") (pinfunction "B_1") (pintype "passive"))
    )
    (net (code "104") (name "/6C") (class "Default")
      (node (ref "IC6") (pin "2") (pinfunction "QC_2") (pintype "tri_state"))
      (node (ref "RN60") (pin "2") (pinfunction "2_2") (pintype "passive"))
    )
    (net (code "105") (name "/6D") (class "Default")
      (node (ref "IC6") (pin "3") (pinfunction "QD_3") (pintype "tri_state"))
      (node (ref "RN60") (pin "1") (pinfunction "1_1") (pintype "passive"))
    )
    (net (code "106") (name "/6E") (class "Default")
      (node (ref "IC6") (pin "4") (pinfunction "QE_4") (pintype "tri_state"))
      (node (ref "RN61") (pin "4") (pinfunction "4_4") (pintype "passive"))
    )
    (net (code "107") (name "/6F") (class "Default")
      (node (ref "IC6") (pin "5") (pinfunction "QF_5") (pintype "tri_state"))
      (node (ref "RN61") (pin "3") (pinfunction "3_3") (pintype "passive"))
    )
    (net (code "108") (name "/6G") (class "Default")
      (node (ref "IC6") (pin "6") (pinfunction "QG_6") (pintype "tri_state"))
      (node (ref "RN61") (pin "2") (pinfunction "2_2") (pintype "passive"))
    )
    (net (code "109") (name "/6H") (class "Default")
      (node (ref "IC6") (pin "7") (pinfunction "QH_7") (pintype "tri_state"))
      (node (ref "RN61") (pin "1") (pinfunction "1_1") (pintype "passive"))
    )
    (net (code "110") (name "/7A") (class "Default")
      (node (ref "IC7") (pin "15") (pinfunction "QA_15") (pintype "tri_state"))
      (node (ref "RN70") (pin "4") (pinfunction "4_4") (pintype "passive"))
    )
    (net (code "111") (name "/7B") (class "Default")
      (node (ref "IC7") (pin "1") (pinfunction "QB_1") (pintype "tri_state"))
      (node (ref "RN70") (pin "3") (pinfunction "3_3") (pintype "passive"))
    )
    (net (code "112") (name "/7C") (class "Default")
      (node (ref "IC7") (pin "2") (pinfunction "QC_2") (pintype "tri_state"))
      (node (ref "RN70") (pin "2") (pinfunction "2_2") (pintype "passive"))
    )
    (net (code "113") (name "/7D") (class "Default")
      (node (ref "IC7") (pin "3") (pinfunction "QD_3") (pintype "tri_state"))
      (node (ref "RN70") (pin "1") (pinfunction "1_1") (pintype "passive"))
    )
    (net (code "114") (name "/7E") (class "Default")
      (node (ref "IC7") (pin "4") (pinfunction "QE_4") (pintype "tri_state"))
      (node (ref "RN71") (pin "4") (pinfunction "4_4") (pintype "passive"))
    )
    (net (code "115") (name "/7F") (class "Default")
      (node (ref "IC7") (pin "5") (pinfunction "QF_5") (pintype "tri_state"))
      (node (ref "RN71") (pin "3") (pinfunction "3_3") (pintype "passive"))
    )
    (net (code "116") (name "/7G") (class "Default")
      (node (ref "IC7") (pin "6") (pinfunction "QG_6") (pintype "tri_state"))
      (node (ref "RN71") (pin "2") (pinfunction "2_2") (pintype "passive"))
    )
    (net (code "117") (name "/7H") (class "Default")
      (node (ref "IC7") (pin "7") (pinfunction "QH_7") (pintype "tri_state"))
      (node (ref "RN71") (pin "1") (pinfunction "1_1") (pintype "passive"))
    )
    (net (code "118") (name "/8A") (class "Default")
      (node (ref "IC8") (pin "15") (pinfunction "QA_15") (pintype "tri_state"))
      (node (ref "RN80") (pin "4") (pinfunction "4_4") (pintype "passive"))
    )
    (net (code "119") (name "/8B") (class "Default")
      (node (ref "IC8") (pin "1") (pinfunction "QB_1") (pintype "tri_state"))
      (node (ref "RN80") (pin "3") (pinfunction "3_3") (pintype "passive"))
    )
    (net (code "120") (name "/8C") (class "Default")
      (node (ref "IC8") (pin "2") (pinfunction "QC_2") (pintype "tri_state"))
      (node (ref "RN80") (pin "2") (pinfunction "2_2") (pintype "passive"))
    )
    (net (code "121") (name "/8D") (class "Default")
      (node (ref "IC8") (pin "3") (pinfunction "QD_3") (pintype "tri_state"))
      (node (ref "RN80") (pin "1") (pinfunction "1_1") (pintype "passive"))
    )
    (net (code "122") (name "/8E") (class "Default")
      (node (ref "IC8") (pin "4") (pinfunction "QE_4") (pintype "tri_state"))
      (node (ref "RN81") (pin "4") (pinfunction "4_4") (pintype "passive"))
    )
    (net (code "123") (name "/8F") (class "Default")
      (node (ref "IC8") (pin "5") (pinfunction "QF_5") (pintype "tri_state"))
      (node (ref "RN81") (pin "3") (pinfunction "3_3") (pintype "passive"))
    )
    (net (code "124") (name "/8G") (class "Default")
      (node (ref "IC8") (pin "6") (pinfunction "QG_6") (pintype "tri_state"))
      (node (ref "RN81") (pin "2") (pinfunction "2_2") (pintype "passive"))
    )
    (net (code "125") (name "/8H") (class "Default")
      (node (ref "IC8") (pin "7") (pinfunction "QH_7") (pintype "tri_state"))
      (node (ref "RN81") (pin "1") (pinfunction "1_1") (pintype "passive"))
    )
    (net (code "126") (name "/EN") (class "Default")
      (node (ref "IC1") (pin "13") (pinfunction "G_13") (pintype "input"))
      (node (ref "IC2") (pin "13") (pinfunction "G_13") (pintype "input"))
      (node (ref "IC3") (pin "13") (pinfunction "G_13") (pintype "input"))
      (node (ref "IC4") (pin "13") (pinfunction "G_13") (pintype "input"))
      (node (ref "IC5") (pin "13") (pinfunction "G_13") (pintype "input"))
      (node (ref "IC6") (pin "13") (pinfunction "G_13") (pintype "input"))
      (node (ref "IC7") (pin "13") (pinfunction "G_13") (pintype "input"))
      (node (ref "IC8") (pin "13") (pinfunction "G_13") (pintype "input"))
      (node (ref "JP1") (pin "1") (pinfunction "1_1") (pintype "passive"))
    )
    (net (code "127") (name "/GL1") (class "Default")
      (node (ref "RN31") (pin "5") (pinfunction "5_5") (pintype "passive"))
      (node (ref "T1") (pin "1") (pinfunction "B_1") (pintype "passive"))
    )
    (net (code "128") (name "/GL2") (class "Default")
      (node (ref "RN31") (pin "6") (pinfunction "6_6") (pintype "passive"))
      (node (ref "T2") (pin "1") (pinfunction "B_1") (pintype "passive"))
    )
    (net (code "129") (name "/GL3") (class "Default")
      (node (ref "RN60") (pin "7") (pinfunction "7_7") (pintype "passive"))
      (node (ref "T3") (pin "1") (pinfunction "B_1") (pintype "passive"))
    )
    (net (code "130") (name "/GL4") (class "Default")
      (node (ref "RN60") (pin "8") (pinfunction "8_8") (pintype "passive"))
      (node (ref "T4") (pin "1") (pinfunction "B_1") (pintype "passive"))
    )
    (net (code "131") (name "/MOSI") (class "Default")
      (node (ref "IC1") (pin "14") (pinfunction "SER_14") (pintype "input"))
      (node (ref "JP1") (pin "4") (pinfunction "4_4") (pintype "passive"))
    )
    (net (code "132") (name "/N1_0") (class "Default")
      (node (ref "N2") (pin "12") (pinfunction "0_12") (pintype "bidirectional"))
      (node (ref "T12") (pin "3") (pinfunction "C_3") (pintype "passive"))
    )
    (net (code "133") (name "/N1_1") (class "Default")
      (node (ref "N2") (pin "1") (pinfunction "1_1") (pintype "bidirectional"))
      (node (ref "T11") (pin "3") (pinfunction "C_3") (pintype "passive"))
    )
    (net (code "134") (name "/N1_2") (class "Default")
      (node (ref "N2") (pin "2") (pinfunction "2_2") (pintype "bidirectional"))
      (node (ref "T10") (pin "3") (pinfunction "C_3") (pintype "passive"))
    )
    (net (code "135") (name "/N1_3") (class "Default")
      (node (ref "N2") (pin "3") (pinfunction "3_3") (pintype "bidirectional"))
      (node (ref "T19") (pin "3") (pinfunction "C_3") (pintype "passive"))
    )
    (net (code "136") (name "/N1_4") (class "Default")
      (node (ref "N2") (pin "5") (pinfunction "4_5") (pintype "bidirectional"))
      (node (ref "T18") (pin "3") (pinfunction "C_3") (pintype "passive"))
    )
    (net (code "137") (name "/N1_5") (class "Default")
      (node (ref "N2") (pin "6") (pinfunction "5_6") (pintype "bidirectional"))
      (node (ref "T17") (pin "3") (pinfunction "C_3") (pintype "passive"))
    )
    (net (code "138") (name "/N1_6") (class "Default")
      (node (ref "N2") (pin "7") (pinfunction "6_7") (pintype "bidirectional"))
      (node (ref "T16") (pin "3") (pinfunction "C_3") (pintype "passive"))
    )
    (net (code "139") (name "/N1_7") (class "Default")
      (node (ref "N2") (pin "8") (pinfunction "7_8") (pintype "bidirectional"))
      (node (ref "T15") (pin "3") (pinfunction "C_3") (pintype "passive"))
    )
    (net (code "140") (name "/N1_8") (class "Default")
      (node (ref "N2") (pin "9") (pinfunction "8_9") (pintype "bidirectional"))
      (node (ref "T14") (pin "3") (pinfunction "C_3") (pintype "passive"))
    )
    (net (code "141") (name "/N1_9") (class "Default")
      (node (ref "N2") (pin "11") (pinfunction "9_11") (pintype "bidirectional"))
      (node (ref "T13") (pin "3") (pinfunction "C_3") (pintype "passive"))
    )
    (net (code "142") (name "/N1_DP") (class "Default")
      (node (ref "N2") (pin "10") (pinfunction "DP_10") (pintype "bidirectional"))
    )
    (net (code "143") (name "/N1_IC") (class "Default")
      (node (ref "N2") (pin "4") (pinfunction "IC_4") (pintype "bidirectional"))
    )
    (net (code "144") (name "/N2_0") (class "Default")
      (node (ref "N1") (pin "12") (pinfunction "0_12") (pintype "bidirectional"))
      (node (ref "T22") (pin "3") (pinfunction "C_3") (pintype "passive"))
    )
    (net (code "145") (name "/N2_1") (class "Default")
      (node (ref "N1") (pin "1") (pinfunction "1_1") (pintype "bidirectional"))
      (node (ref "T21") (pin "3") (pinfunction "C_3") (pintype "passive"))
    )
    (net (code "146") (name "/N2_2") (class "Default")
      (node (ref "N1") (pin "2") (pinfunction "2_2") (pintype "bidirectional"))
      (node (ref "T20") (pin "3") (pinfunction "C_3") (pintype "passive"))
    )
    (net (code "147") (name "/N2_3") (class "Default")
      (node (ref "N1") (pin "3") (pinfunction "3_3") (pintype "bidirectional"))
      (node (ref "T29") (pin "3") (pinfunction "C_3") (pintype "passive"))
    )
    (net (code "148") (name "/N2_4") (class "Default")
      (node (ref "N1") (pin "5") (pinfunction "4_5") (pintype "bidirectional"))
      (node (ref "T28") (pin "3") (pinfunction "C_3") (pintype "passive"))
    )
    (net (code "149") (name "/N2_5") (class "Default")
      (node (ref "N1") (pin "6") (pinfunction "5_6") (pintype "bidirectional"))
      (node (ref "T27") (pin "3") (pinfunction "C_3") (pintype "passive"))
    )
    (net (code "150") (name "/N2_6") (class "Default")
      (node (ref "N1") (pin "7") (pinfunction "6_7") (pintype "bidirectional"))
      (node (ref "T26") (pin "3") (pinfunction "C_3") (pintype "passive"))
    )
    (net (code "151") (name "/N2_7") (class "Default")
      (node (ref "N1") (pin "8") (pinfunction "7_8") (pintype "bidirectional"))
      (node (ref "T25") (pin "3") (pinfunction "C_3") (pintype "passive"))
    )
    (net (code "152") (name "/N2_8") (class "Default")
      (node (ref "N1") (pin "9") (pinfunction "8_9") (pintype "bidirectional"))
      (node (ref "T24") (pin "3") (pinfunction "C_3") (pintype "passive"))
    )
    (net (code "153") (name "/N2_9") (class "Default")
      (node (ref "N1") (pin "11") (pinfunction "9_11") (pintype "bidirectional"))
      (node (ref "T23") (pin "3") (pinfunction "C_3") (pintype "passive"))
    )
    (net (code "154") (name "/N3_0") (class "Default")
      (node (ref "N3") (pin "12") (pinfunction "0_12") (pintype "bidirectional"))
      (node (ref "T32") (pin "3") (pinfunction "C_3") (pintype "passive"))
    )
    (net (code "155") (name "/N3_1") (class "Default")
      (node (ref "N3") (pin "1") (pinfunction "1_1") (pintype "bidirectional"))
      (node (ref "T31") (pin "3") (pinfunction "C_3") (pintype "passive"))
    )
    (net (code "156") (name "/N3_2") (class "Default")
      (node (ref "N3") (pin "2") (pinfunction "2_2") (pintype "bidirectional"))
      (node (ref "T30") (pin "3") (pinfunction "C_3") (pintype "passive"))
    )
    (net (code "157") (name "/N3_3") (class "Default")
      (node (ref "N3") (pin "3") (pinfunction "3_3") (pintype "bidirectional"))
      (node (ref "T39") (pin "3") (pinfunction "C_3") (pintype "passive"))
    )
    (net (code "158") (name "/N3_4") (class "Default")
      (node (ref "N3") (pin "5") (pinfunction "4_5") (pintype "bidirectional"))
      (node (ref "T38") (pin "3") (pinfunction "C_3") (pintype "passive"))
    )
    (net (code "159") (name "/N3_5") (class "Default")
      (node (ref "N3") (pin "6") (pinfunction "5_6") (pintype "bidirectional"))
      (node (ref "T37") (pin "3") (pinfunction "C_3") (pintype "passive"))
    )
    (net (code "160") (name "/N3_6") (class "Default")
      (node (ref "N3") (pin "7") (pinfunction "6_7") (pintype "bidirectional"))
      (node (ref "T36") (pin "3") (pinfunction "C_3") (pintype "passive"))
    )
    (net (code "161") (name "/N3_7") (class "Default")
      (node (ref "N3") (pin "8") (pinfunction "7_8") (pintype "bidirectional"))
      (node (ref "T35") (pin "3") (pinfunction "C_3") (pintype "passive"))
    )
    (net (code "162") (name "/N3_8") (class "Default")
      (node (ref "N3") (pin "9") (pinfunction "8_9") (pintype "bidirectional"))
      (node (ref "T34") (pin "3") (pinfunction "C_3") (pintype "passive"))
    )
    (net (code "163") (name "/N3_9") (class "Default")
      (node (ref "N3") (pin "11") (pinfunction "9_11") (pintype "bidirectional"))
      (node (ref "T33") (pin "3") (pinfunction "C_3") (pintype "passive"))
    )
    (net (code "164") (name "/N4_0") (class "Default")
      (node (ref "N4") (pin "12") (pinfunction "0_12") (pintype "bidirectional"))
      (node (ref "T42") (pin "3") (pinfunction "C_3") (pintype "passive"))
    )
    (net (code "165") (name "/N4_1") (class "Default")
      (node (ref "N4") (pin "1") (pinfunction "1_1") (pintype "bidirectional"))
      (node (ref "T41") (pin "3") (pinfunction "C_3") (pintype "passive"))
    )
    (net (code "166") (name "/N4_2") (class "Default")
      (node (ref "N4") (pin "2") (pinfunction "2_2") (pintype "bidirectional"))
      (node (ref "T40") (pin "3") (pinfunction "C_3") (pintype "passive"))
    )
    (net (code "167") (name "/N4_3") (class "Default")
      (node (ref "N4") (pin "3") (pinfunction "3_3") (pintype "bidirectional"))
      (node (ref "T49") (pin "3") (pinfunction "C_3") (pintype "passive"))
    )
    (net (code "168") (name "/N4_4") (class "Default")
      (node (ref "N4") (pin "5") (pinfunction "4_5") (pintype "bidirectional"))
      (node (ref "T48") (pin "3") (pinfunction "C_3") (pintype "passive"))
    )
    (net (code "169") (name "/N4_5") (class "Default")
      (node (ref "N4") (pin "6") (pinfunction "5_6") (pintype "bidirectional"))
      (node (ref "T47") (pin "3") (pinfunction "C_3") (pintype "passive"))
    )
    (net (code "170") (name "/N4_6") (class "Default")
      (node (ref "N4") (pin "7") (pinfunction "6_7") (pintype "bidirectional"))
      (node (ref "T46") (pin "3") (pinfunction "C_3") (pintype "passive"))
    )
    (net (code "171") (name "/N4_7") (class "Default")
      (node (ref "N4") (pin "8") (pinfunction "7_8") (pintype "bidirectional"))
      (node (ref "T45") (pin "3") (pinfunction "C_3") (pintype "passive"))
    )
    (net (code "172") (name "/N4_8") (class "Default")
      (node (ref "N4") (pin "9") (pinfunction "8_9") (pintype "bidirectional"))
      (node (ref "T44") (pin "3") (pinfunction "C_3") (pintype "passive"))
    )
    (net (code "173") (name "/N4_9") (class "Default")
      (node (ref "N4") (pin "11") (pinfunction "9_11") (pintype "bidirectional"))
      (node (ref "T43") (pin "3") (pinfunction "C_3") (pintype "passive"))
    )
    (net (code "174") (name "/N5_0") (class "Default")
      (node (ref "N5") (pin "12") (pinfunction "0_12") (pintype "bidirectional"))
      (node (ref "T52") (pin "3") (pinfunction "C_3") (pintype "passive"))
    )
    (net (code "175") (name "/N5_1") (class "Default")
      (node (ref "N5") (pin "1") (pinfunction "1_1") (pintype "bidirectional"))
      (node (ref "T51") (pin "3") (pinfunction "C_3") (pintype "passive"))
    )
    (net (code "176") (name "/N5_2") (class "Default")
      (node (ref "N5") (pin "2") (pinfunction "2_2") (pintype "bidirectional"))
      (node (ref "T50") (pin "3") (pinfunction "C_3") (pintype "passive"))
    )
    (net (code "177") (name "/N5_3") (class "Default")
      (node (ref "N5") (pin "3") (pinfunction "3_3") (pintype "bidirectional"))
      (node (ref "T59") (pin "3") (pinfunction "C_3") (pintype "passive"))
    )
    (net (code "178") (name "/N5_4") (class "Default")
      (node (ref "N5") (pin "5") (pinfunction "4_5") (pintype "bidirectional"))
      (node (ref "T58") (pin "3") (pinfunction "C_3") (pintype "passive"))
    )
    (net (code "179") (name "/N5_5") (class "Default")
      (node (ref "N5") (pin "6") (pinfunction "5_6") (pintype "bidirectional"))
      (node (ref "T57") (pin "3") (pinfunction "C_3") (pintype "passive"))
    )
    (net (code "180") (name "/N5_6") (class "Default")
      (node (ref "N5") (pin "7") (pinfunction "6_7") (pintype "bidirectional"))
      (node (ref "T56") (pin "3") (pinfunction "C_3") (pintype "passive"))
    )
    (net (code "181") (name "/N5_7") (class "Default")
      (node (ref "N5") (pin "8") (pinfunction "7_8") (pintype "bidirectional"))
      (node (ref "T55") (pin "3") (pinfunction "C_3") (pintype "passive"))
    )
    (net (code "182") (name "/N5_8") (class "Default")
      (node (ref "N5") (pin "9") (pinfunction "8_9") (pintype "bidirectional"))
      (node (ref "T54") (pin "3") (pinfunction "C_3") (pintype "passive"))
    )
    (net (code "183") (name "/N5_9") (class "Default")
      (node (ref "N5") (pin "11") (pinfunction "9_11") (pintype "bidirectional"))
      (node (ref "T53") (pin "3") (pinfunction "C_3") (pintype "passive"))
    )
    (net (code "184") (name "/N6_0") (class "Default")
      (node (ref "N6") (pin "12") (pinfunction "0_12") (pintype "bidirectional"))
      (node (ref "T62") (pin "3") (pinfunction "C_3") (pintype "passive"))
    )
    (net (code "185") (name "/N6_1") (class "Default")
      (node (ref "N6") (pin "1") (pinfunction "1_1") (pintype "bidirectional"))
      (node (ref "T61") (pin "3") (pinfunction "C_3") (pintype "passive"))
    )
    (net (code "186") (name "/N6_2") (class "Default")
      (node (ref "N6") (pin "2") (pinfunction "2_2") (pintype "bidirectional"))
      (node (ref "T60") (pin "3") (pinfunction "C_3") (pintype "passive"))
    )
    (net (code "187") (name "/N6_3") (class "Default")
      (node (ref "N6") (pin "3") (pinfunction "3_3") (pintype "bidirectional"))
      (node (ref "T69") (pin "3") (pinfunction "C_3") (pintype "passive"))
    )
    (net (code "188") (name "/N6_4") (class "Default")
      (node (ref "N6") (pin "5") (pinfunction "4_5") (pintype "bidirectional"))
      (node (ref "T68") (pin "3") (pinfunction "C_3") (pintype "passive"))
    )
    (net (code "189") (name "/N6_5") (class "Default")
      (node (ref "N6") (pin "6") (pinfunction "5_6") (pintype "bidirectional"))
      (node (ref "T67") (pin "3") (pinfunction "C_3") (pintype "passive"))
    )
    (net (code "190") (name "/N6_6") (class "Default")
      (node (ref "N6") (pin "7") (pinfunction "6_7") (pintype "bidirectional"))
      (node (ref "T66") (pin "3") (pinfunction "C_3") (pintype "passive"))
    )
    (net (code "191") (name "/N6_7") (class "Default")
      (node (ref "N6") (pin "8") (pinfunction "7_8") (pintype "bidirectional"))
      (node (ref "T65") (pin "3") (pinfunction "C_3") (pintype "passive"))
    )
    (net (code "192") (name "/N6_8") (class "Default")
      (node (ref "N6") (pin "9") (pinfunction "8_9") (pintype "bidirectional"))
      (node (ref "T64") (pin "3") (pinfunction "C_3") (pintype "passive"))
    )
    (net (code "193") (name "/N6_9") (class "Default")
      (node (ref "N6") (pin "11") (pinfunction "9_11") (pintype "bidirectional"))
      (node (ref "T63") (pin "3") (pinfunction "C_3") (pintype "passive"))
    )
    (net (code "194") (name "/RCK") (class "Default")
      (node (ref "IC1") (pin "12") (pinfunction "RCK_12") (pintype "input"))
      (node (ref "IC2") (pin "12") (pinfunction "RCK_12") (pintype "input"))
      (node (ref "IC3") (pin "12") (pinfunction "RCK_12") (pintype "input"))
      (node (ref "IC4") (pin "12") (pinfunction "RCK_12") (pintype "input"))
      (node (ref "IC5") (pin "12") (pinfunction "RCK_12") (pintype "input"))
      (node (ref "IC6") (pin "12") (pinfunction "RCK_12") (pintype "input"))
      (node (ref "IC7") (pin "12") (pinfunction "RCK_12") (pintype "input"))
      (node (ref "IC8") (pin "12") (pinfunction "RCK_12") (pintype "input"))
      (node (ref "JP1") (pin "5") (pinfunction "5_5") (pintype "passive"))
    )
    (net (code "195") (name "/SCK") (class "Default")
      (node (ref "IC1") (pin "11") (pinfunction "SCK_11") (pintype "input"))
      (node (ref "IC2") (pin "11") (pinfunction "SCK_11") (pintype "input"))
      (node (ref "IC3") (pin "11") (pinfunction "SCK_11") (pintype "input"))
      (node (ref "IC4") (pin "11") (pinfunction "SCK_11") (pintype "input"))
      (node (ref "IC5") (pin "11") (pinfunction "SCK_11") (pintype "input"))
      (node (ref "IC6") (pin "11") (pinfunction "SCK_11") (pintype "input"))
      (node (ref "IC7") (pin "11") (pinfunction "SCK_11") (pintype "input"))
      (node (ref "IC8") (pin "11") (pinfunction "SCK_11") (pintype "input"))
      (node (ref "JP1") (pin "3") (pinfunction "3_3") (pintype "passive"))
    )
    (net (code "196") (name "/SCL") (class "Default")
      (node (ref "IC1") (pin "10") (pinfunction "SCL_10") (pintype "input"))
      (node (ref "IC2") (pin "10") (pinfunction "SCL_10") (pintype "input"))
      (node (ref "IC3") (pin "10") (pinfunction "SCL_10") (pintype "input"))
      (node (ref "IC4") (pin "10") (pinfunction "SCL_10") (pintype "input"))
      (node (ref "IC5") (pin "10") (pinfunction "SCL_10") (pintype "input"))
      (node (ref "IC6") (pin "10") (pinfunction "SCL_10") (pintype "input"))
      (node (ref "IC7") (pin "10") (pinfunction "SCL_10") (pintype "input"))
      (node (ref "IC8") (pin "10") (pinfunction "SCL_10") (pintype "input"))
      (node (ref "JP1") (pin "2") (pinfunction "2_2") (pintype "passive"))
    )
    (net (code "197") (name "GND") (class "Default")
      (node (ref "C1") (pin "2") (pinfunction "2_2") (pintype "passive"))
      (node (ref "C2") (pin "2") (pinfunction "2_2") (pintype "passive"))
      (node (ref "C3") (pin "2") (pinfunction "2_2") (pintype "passive"))
      (node (ref "C4") (pin "2") (pinfunction "2_2") (pintype "passive"))
      (node (ref "C5") (pin "2") (pinfunction "2_2") (pintype "passive"))
      (node (ref "C6") (pin "2") (pinfunction "2_2") (pintype "passive"))
      (node (ref "C7") (pin "2") (pinfunction "2_2") (pintype "passive"))
      (node (ref "C8") (pin "2") (pinfunction "2_2") (pintype "passive"))
      (node (ref "IC1") (pin "8") (pinfunction "GND_8") (pintype "power_in"))
      (node (ref "IC2") (pin "8") (pinfunction "GND_8") (pintype "power_in"))
      (node (ref "IC3") (pin "8") (pinfunction "GND_8") (pintype "power_in"))
      (node (ref "IC4") (pin "8") (pinfunction "GND_8") (pintype "power_in"))
      (node (ref "IC5") (pin "8") (pinfunction "GND_8") (pintype "power_in"))
      (node (ref "IC6") (pin "8") (pinfunction "GND_8") (pintype "power_in"))
      (node (ref "IC7") (pin "8") (pinfunction "GND_8") (pintype "power_in"))
      (node (ref "IC8") (pin "8") (pinfunction "GND_8") (pintype "power_in"))
      (node (ref "JP1") (pin "6") (pinfunction "6_6") (pintype "passive"))
      (node (ref "JP2") (pin "3") (pinfunction "3_3") (pintype "passive"))
      (node (ref "JP2") (pin "4") (pinfunction "4_4") (pintype "passive"))
      (node (ref "T1") (pin "2") (pinfunction "E_2") (pintype "passive"))
      (node (ref "T10") (pin "2") (pinfunction "E_2") (pintype "passive"))
      (node (ref "T11") (pin "2") (pinfunction "E_2") (pintype "passive"))
      (node (ref "T12") (pin "2") (pinfunction "E_2") (pintype "passive"))
      (node (ref "T13") (pin "2") (pinfunction "E_2") (pintype "passive"))
      (node (ref "T14") (pin "2") (pinfunction "E_2") (pintype "passive"))
      (node (ref "T15") (pin "2") (pinfunction "E_2") (pintype "passive"))
      (node (ref "T16") (pin "2") (pinfunction "E_2") (pintype "passive"))
      (node (ref "T17") (pin "2") (pinfunction "E_2") (pintype "passive"))
      (node (ref "T18") (pin "2") (pinfunction "E_2") (pintype "passive"))
      (node (ref "T19") (pin "2") (pinfunction "E_2") (pintype "passive"))
      (node (ref "T2") (pin "2") (pinfunction "E_2") (pintype "passive"))
      (node (ref "T20") (pin "2") (pinfunction "E_2") (pintype "passive"))
      (node (ref "T21") (pin "2") (pinfunction "E_2") (pintype "passive"))
      (node (ref "T22") (pin "2") (pinfunction "E_2") (pintype "passive"))
      (node (ref "T23") (pin "2") (pinfunction "E_2") (pintype "passive"))
      (node (ref "T24") (pin "2") (pinfunction "E_2") (pintype "passive"))
      (node (ref "T25") (pin "2") (pinfunction "E_2") (pintype "passive"))
      (node (ref "T26") (pin "2") (pinfunction "E_2") (pintype "passive"))
      (node (ref "T27") (pin "2") (pinfunction "E_2") (pintype "passive"))
      (node (ref "T28") (pin "2") (pinfunction "E_2") (pintype "passive"))
      (node (ref "T29") (pin "2") (pinfunction "E_2") (pintype "passive"))
      (node (ref "T3") (pin "2") (pinfunction "E_2") (pintype "passive"))
      (node (ref "T30") (pin "2") (pinfunction "E_2") (pintype "passive"))
      (node (ref "T31") (pin "2") (pinfunction "E_2") (pintype "passive"))
      (node (ref "T32") (pin "2") (pinfunction "E_2") (pintype "passive"))
      (node (ref "T33") (pin "2") (pinfunction "E_2") (pintype "passive"))
      (node (ref "T34") (pin "2") (pinfunction "E_2") (pintype "passive"))
      (node (ref "T35") (pin "2") (pinfunction "E_2") (pintype "passive"))
      (node (ref "T36") (pin "2") (pinfunction "E_2") (pintype "passive"))
      (node (ref "T37") (pin "2") (pinfunction "E_2") (pintype "passive"))
      (node (ref "T38") (pin "2") (pinfunction "E_2") (pintype "passive"))
      (node (ref "T39") (pin "2") (pinfunction "E_2") (pintype "passive"))
      (node (ref "T4") (pin "2") (pinfunction "E_2") (pintype "passive"))
      (node (ref "T40") (pin "2") (pinfunction "E_2") (pintype "passive"))
      (node (ref "T41") (pin "2") (pinfunction "E_2") (pintype "passive"))
      (node (ref "T42") (pin "2") (pinfunction "E_2") (pintype "passive"))
      (node (ref "T43") (pin "2") (pinfunction "E_2") (pintype "passive"))
      (node (ref "T44") (pin "2") (pinfunction "E_2") (pintype "passive"))
      (node (ref "T45") (pin "2") (pinfunction "E_2") (pintype "passive"))
      (node (ref "T46") (pin "2") (pinfunction "E_2") (pintype "passive"))
      (node (ref "T47") (pin "2") (pinfunction "E_2") (pintype "passive"))
      (node (ref "T48") (pin "2") (pinfunction "E_2") (pintype "passive"))
      (node (ref "T49") (pin "2") (pinfunction "E_2") (pintype "passive"))
      (node (ref "T50") (pin "2") (pinfunction "E_2") (pintype "passive"))
      (node (ref "T51") (pin "2") (pinfunction "E_2") (pintype "passive"))
      (node (ref "T52") (pin "2") (pinfunction "E_2") (pintype "passive"))
      (node (ref "T53") (pin "2") (pinfunction "E_2") (pintype "passive"))
      (node (ref "T54") (pin "2") (pinfunction "E_2") (pintype "passive"))
      (node (ref "T55") (pin "2") (pinfunction "E_2") (pintype "passive"))
      (node (ref "T56") (pin "2") (pinfunction "E_2") (pintype "passive"))
      (node (ref "T57") (pin "2") (pinfunction "E_2") (pintype "passive"))
      (node (ref "T58") (pin "2") (pinfunction "E_2") (pintype "passive"))
      (node (ref "T59") (pin "2") (pinfunction "E_2") (pintype "passive"))
      (node (ref "T60") (pin "2") (pinfunction "E_2") (pintype "passive"))
      (node (ref "T61") (pin "2") (pinfunction "E_2") (pintype "passive"))
      (node (ref "T62") (pin "2") (pinfunction "E_2") (pintype "passive"))
      (node (ref "T63") (pin "2") (pinfunction "E_2") (pintype "passive"))
      (node (ref "T64") (pin "2") (pinfunction "E_2") (pintype "passive"))
      (node (ref "T65") (pin "2") (pinfunction "E_2") (pintype "passive"))
      (node (ref "T66") (pin "2") (pinfunction "E_2") (pintype "passive"))
      (node (ref "T67") (pin "2") (pinfunction "E_2") (pintype "passive"))
      (node (ref "T68") (pin "2") (pinfunction "E_2") (pintype "passive"))
      (node (ref "T69") (pin "2") (pinfunction "E_2") (pintype "passive"))
    )
    (net (code "198") (name "Net-(GL1-A)") (class "Default")
      (node (ref "GL1") (pin "1") (pinfunction "A_1") (pintype "passive"))
      (node (ref "R1") (pin "1") (pinfunction "1_1") (pintype "passive"))
    )
    (net (code "199") (name "Net-(GL1-A1)") (class "Default")
      (node (ref "GL1") (pin "2") (pinfunction "A1_2") (pintype "passive"))
      (node (ref "T1") (pin "3") (pinfunction "C_3") (pintype "passive"))
    )
    (net (code "200") (name "Net-(GL2-A)") (class "Default")
      (node (ref "GL2") (pin "1") (pinfunction "A_1") (pintype "passive"))
      (node (ref "R2") (pin "1") (pinfunction "1_1") (pintype "passive"))
    )
    (net (code "201") (name "Net-(GL2-A1)") (class "Default")
      (node (ref "GL2") (pin "2") (pinfunction "A1_2") (pintype "passive"))
      (node (ref "T2") (pin "3") (pinfunction "C_3") (pintype "passive"))
    )
    (net (code "202") (name "Net-(GL3-A)") (class "Default")
      (node (ref "GL3") (pin "1") (pinfunction "A_1") (pintype "passive"))
      (node (ref "R3") (pin "1") (pinfunction "1_1") (pintype "passive"))
    )
    (net (code "203") (name "Net-(GL3-A1)") (class "Default")
      (node (ref "GL3") (pin "2") (pinfunction "A1_2") (pintype "passive"))
      (node (ref "T3") (pin "3") (pinfunction "C_3") (pintype "passive"))
    )
    (net (code "204") (name "Net-(GL4-A)") (class "Default")
      (node (ref "GL4") (pin "1") (pinfunction "A_1") (pintype "passive"))
      (node (ref "R4") (pin "1") (pinfunction "1_1") (pintype "passive"))
    )
    (net (code "205") (name "Net-(GL4-A1)") (class "Default")
      (node (ref "GL4") (pin "2") (pinfunction "A1_2") (pintype "passive"))
      (node (ref "T4") (pin "3") (pinfunction "C_3") (pintype "passive"))
    )
    (net (code "206") (name "Net-(IC1A-QH*)") (class "Default")
      (node (ref "IC1") (pin "9") (pinfunction "QH*_9") (pintype "tri_state"))
      (node (ref "IC2") (pin "14") (pinfunction "SER_14") (pintype "input"))
    )
    (net (code "207") (name "Net-(IC2A-QH*)") (class "Default")
      (node (ref "IC2") (pin "9") (pinfunction "QH*_9") (pintype "tri_state"))
      (node (ref "IC3") (pin "14") (pinfunction "SER_14") (pintype "input"))
    )
    (net (code "208") (name "Net-(IC3A-QH*)") (class "Default")
      (node (ref "IC3") (pin "9") (pinfunction "QH*_9") (pintype "tri_state"))
      (node (ref "IC4") (pin "14") (pinfunction "SER_14") (pintype "input"))
    )
    (net (code "209") (name "Net-(IC4A-QH*)") (class "Default")
      (node (ref "IC4") (pin "9") (pinfunction "QH*_9") (pintype "tri_state"))
      (node (ref "IC5") (pin "14") (pinfunction "SER_14") (pintype "input"))
    )
    (net (code "210") (name "Net-(IC5A-QH*)") (class "Default")
      (node (ref "IC5") (pin "9") (pinfunction "QH*_9") (pintype "tri_state"))
      (node (ref "IC6") (pin "14") (pinfunction "SER_14") (pintype "input"))
    )
    (net (code "211") (name "Net-(IC6A-QH*)") (class "Default")
      (node (ref "IC6") (pin "9") (pinfunction "QH*_9") (pintype "tri_state"))
      (node (ref "IC7") (pin "14") (pinfunction "SER_14") (pintype "input"))
    )
    (net (code "212") (name "Net-(IC7A-QH*)") (class "Default")
      (node (ref "IC7") (pin "9") (pinfunction "QH*_9") (pintype "tri_state"))
      (node (ref "IC8") (pin "14") (pinfunction "SER_14") (pintype "input"))
    )
    (net (code "213") (name "Net-(N1-A)") (class "Default")
      (node (ref "N1") (pin "13") (pinfunction "A_13") (pintype "bidirectional"))
      (node (ref "R20") (pin "1") (pinfunction "1_1") (pintype "passive"))
    )
    (net (code "214") (name "Net-(N2-A)") (class "Default")
      (node (ref "N2") (pin "13") (pinfunction "A_13") (pintype "bidirectional"))
      (node (ref "R10") (pin "1") (pinfunction "1_1") (pintype "passive"))
    )
    (net (code "215") (name "Net-(N3-A)") (class "Default")
      (node (ref "N3") (pin "13") (pinfunction "A_13") (pintype "bidirectional"))
      (node (ref "R30") (pin "1") (pinfunction "1_1") (pintype "passive"))
    )
    (net (code "216") (name "Net-(N4-A)") (class "Default")
      (node (ref "N4") (pin "13") (pinfunction "A_13") (pintype "bidirectional"))
      (node (ref "R40") (pin "1") (pinfunction "1_1") (pintype "passive"))
    )
    (net (code "217") (name "Net-(N5-A)") (class "Default")
      (node (ref "N5") (pin "13") (pinfunction "A_13") (pintype "bidirectional"))
      (node (ref "R50") (pin "1") (pinfunction "1_1") (pintype "passive"))
    )
    (net (code "218") (name "Net-(N6-A)") (class "Default")
      (node (ref "N6") (pin "13") (pinfunction "A_13") (pintype "bidirectional"))
      (node (ref "R60") (pin "1") (pinfunction "1_1") (pintype "passive"))
    )
    (net (code "219") (name "VDD") (class "Default")
      (node (ref "JP2") (pin "1") (pinfunction "1_1") (pintype "passive"))
      (node (ref "JP2") (pin "2") (pinfunction "2_2") (pintype "passive"))
      (node (ref "R1") (pin "2") (pinfunction "2_2") (pintype "passive"))
      (node (ref "R10") (pin "2") (pinfunction "2_2") (pintype "passive"))
      (node (ref "R2") (pin "2") (pinfunction "2_2") (pintype "passive"))
      (node (ref "R20") (pin "2") (pinfunction "2_2") (pintype "passive"))
      (node (ref "R3") (pin "2") (pinfunction "2_2") (pintype "passive"))
      (node (ref "R30") (pin "2") (pinfunction "2_2") (pintype "passive"))
      (node (ref "R4") (pin "2") (pinfunction "2_2") (pintype "passive"))
      (node (ref "R40") (pin "2") (pinfunction "2_2") (pintype "passive"))
      (node (ref "R50") (pin "2") (pinfunction "2_2") (pintype "passive"))
      (node (ref "R60") (pin "2") (pinfunction "2_2") (pintype "passive"))
    )
    (net (code "220") (name "unconnected-(IC8A-QH*-Pad9)") (class "Default")
      (node (ref "IC8") (pin "9") (pinfunction "QH*_9") (pintype "tri_state"))
    )
    (net (code "221") (name "unconnected-(N1-DP-Pad10)") (class "Default")
      (node (ref "N1") (pin "10") (pinfunction "DP_10") (pintype "bidirectional"))
    )
    (net (code "222") (name "unconnected-(N1-IC-Pad4)") (class "Default")
      (node (ref "N1") (pin "4") (pinfunction "IC_4") (pintype "bidirectional"))
    )
    (net (code "223") (name "unconnected-(N3-DP-Pad10)") (class "Default")
      (node (ref "N3") (pin "10") (pinfunction "DP_10") (pintype "bidirectional"))
    )
    (net (code "224") (name "unconnected-(N3-IC-Pad4)") (class "Default")
      (node (ref "N3") (pin "4") (pinfunction "IC_4") (pintype "bidirectional"))
    )
    (net (code "225") (name "unconnected-(N4-DP-Pad10)") (class "Default")
      (node (ref "N4") (pin "10") (pinfunction "DP_10") (pintype "bidirectional"))
    )
    (net (code "226") (name "unconnected-(N4-IC-Pad4)") (class "Default")
      (node (ref "N4") (pin "4") (pinfunction "IC_4") (pintype "bidirectional"))
    )
    (net (code "227") (name "unconnected-(N5-DP-Pad10)") (class "Default")
      (node (ref "N5") (pin "10") (pinfunction "DP_10") (pintype "bidirectional"))
    )
    (net (code "228") (name "unconnected-(N5-IC-Pad4)") (class "Default")
      (node (ref "N5") (pin "4") (pinfunction "IC_4") (pintype "bidirectional"))
    )
    (net (code "229") (name "unconnected-(N6-DP-Pad10)") (class "Default")
      (node (ref "N6") (pin "10") (pinfunction "DP_10") (pintype "bidirectional"))
    )
    (net (code "230") (name "unconnected-(N6-IC-Pad4)") (class "Default")
      (node (ref "N6") (pin "4") (pinfunction "IC_4") (pintype "bidirectional"))
    )
  )
)
